# SSB_Transceiver_Driver_Amplifier.net
KiCad netlist of a schematic drawn in EAGLE
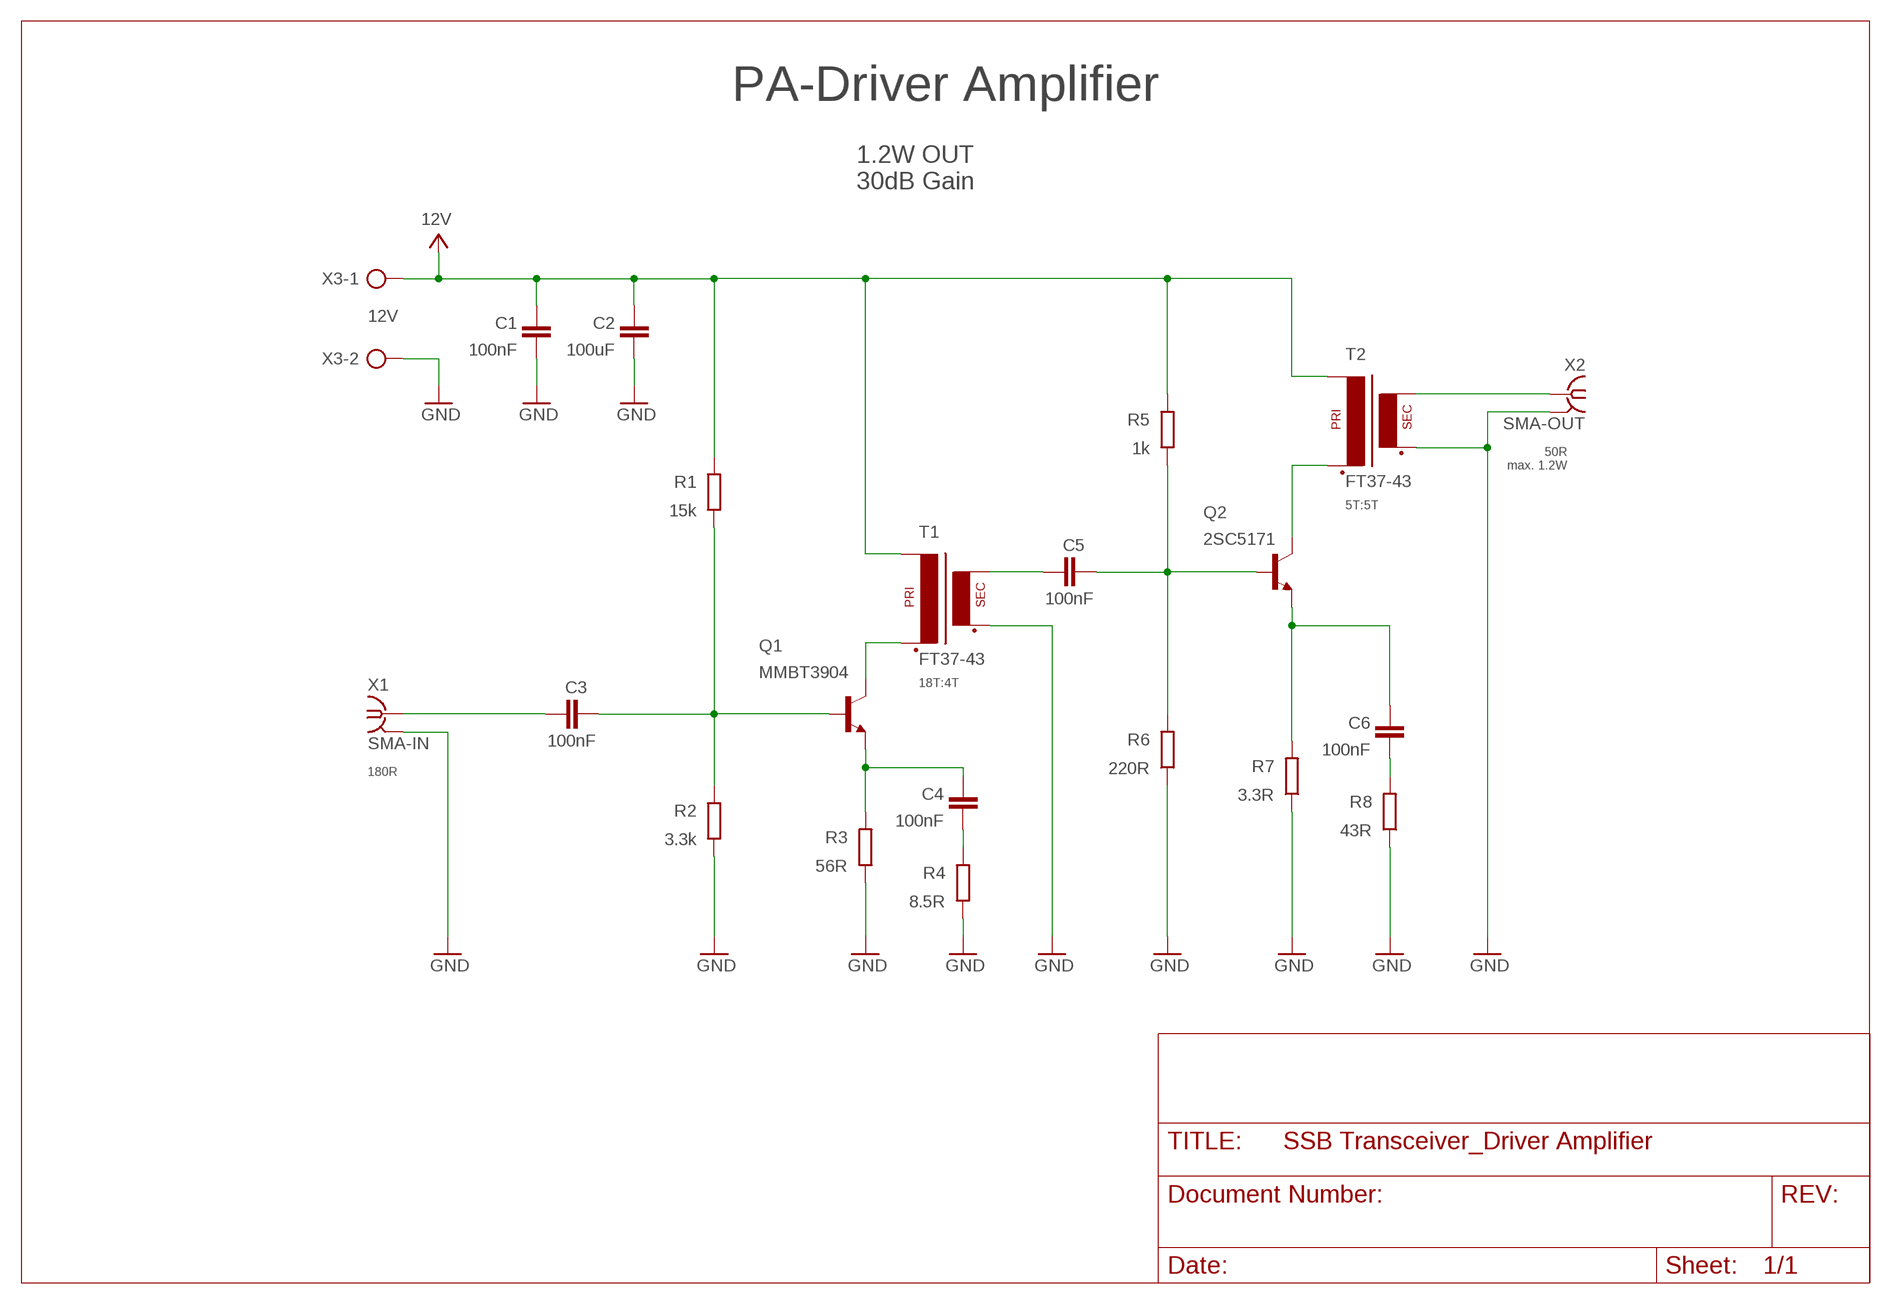
[diagram p0: schematic, sheet 1]

(export (version "E")
  (design (tool "Eeschema 10.0.6"))
  (components
    (comp (ref "C1")
      (value "100nF")
      (footprint "eagle-import:C0805")
      (libsource (lib "eagle-import") (part "C-EUC0805"))
    )
    (comp (ref "C2")
      (value "100uF")
      (footprint "eagle-import:C0805")
      (libsource (lib "eagle-import") (part "C-EUC0805"))
    )
    (comp (ref "C3")
      (value "100nF")
      (footprint "eagle-import:C0805")
      (libsource (lib "eagle-import") (part "C-EUC0805"))
    )
    (comp (ref "C4")
      (value "100nF")
      (footprint "eagle-import:C0805")
      (libsource (lib "eagle-import") (part "C-EUC0805"))
    )
    (comp (ref "C5")
      (value "100nF")
      (footprint "eagle-import:C0805")
      (libsource (lib "eagle-import") (part "C-EUC0805"))
    )
    (comp (ref "C6")
      (value "100nF")
      (footprint "eagle-import:C0805")
      (libsource (lib "eagle-import") (part "C-EUC0805"))
    )
    (comp (ref "Q1")
      (value "MMBT3904")
      (footprint "eagle-import:SOT23-BEC")
      (libsource (lib "eagle-import") (part "-NPN-SOT23-BECMMBT3904LT1"))
    )
    (comp (ref "Q2")
      (value "2SC5171")
      (footprint "eagle-import:TO220")
      (libsource (lib "eagle-import") (part "TIP31B"))
    )
    (comp (ref "R1")
      (value "15k")
      (footprint "eagle-import:R0805")
      (libsource (lib "eagle-import") (part "R-EU_R0805"))
    )
    (comp (ref "R2")
      (value "3.3k")
      (footprint "eagle-import:R0805")
      (libsource (lib "eagle-import") (part "R-EU_R0805"))
    )
    (comp (ref "R3")
      (value "56R")
      (footprint "eagle-import:R0805")
      (libsource (lib "eagle-import") (part "R-EU_R0805"))
    )
    (comp (ref "R4")
      (value "8.5R")
      (footprint "eagle-import:R0805")
      (libsource (lib "eagle-import") (part "R-EU_R0805"))
    )
    (comp (ref "R5")
      (value "1k")
      (footprint "eagle-import:R0805")
      (libsource (lib "eagle-import") (part "R-EU_R0805"))
    )
    (comp (ref "R6")
      (value "220R")
      (footprint "eagle-import:R0805")
      (libsource (lib "eagle-import") (part "R-EU_R0805"))
    )
    (comp (ref "R7")
      (value "3.3R")
      (footprint "eagle-import:R0805")
      (libsource (lib "eagle-import") (part "R-EU_R0805"))
    )
    (comp (ref "R8")
      (value "43R")
      (footprint "eagle-import:R0805")
      (libsource (lib "eagle-import") (part "R-EU_R0805"))
    )
    (comp (ref "T1")
      (value "FT37-43")
      (footprint "eagle-import:FT37-43SMD")
      (libsource (lib "eagle-import") (part "FT37-43"))
    )
    (comp (ref "T2")
      (value "FT37-43")
      (footprint "eagle-import:FT37-43SMD")
      (libsource (lib "eagle-import") (part "FT37-43"))
    )
    (comp (ref "X1")
      (value "SMA-IN")
      (footprint "eagle-import:J502-ND-142-0711-821_826")
      (fields (field (name "MF") "JOHNSON COMPONENTS") (field (name "MPN") "142-0711-821"))
      (libsource (lib "eagle-import") (part "SMA-PCB-CON142-0711-821/826"))
    )
    (comp (ref "X2")
      (value "SMA-OUT")
      (footprint "eagle-import:J502-ND-142-0711-821_826")
      (fields (field (name "MF") "JOHNSON COMPONENTS") (field (name "MPN") "142-0711-821"))
      (libsource (lib "eagle-import") (part "SMA-PCB-CON142-0711-821/826"))
    )
    (comp (ref "X3")
      (value "12V")
      (footprint "eagle-import:AK300_2")
      (libsource (lib "eagle-import") (part "AK300/2"))
    )
  )
  (nets
    (net (code "1") (name "12V") (class "Default")
      (node (ref "C1") (pin "2") (pinfunction "2_2") (pintype "passive"))
      (node (ref "C2") (pin "2") (pinfunction "2_2") (pintype "passive"))
      (node (ref "R1") (pin "1") (pinfunction "1_1") (pintype "passive"))
      (node (ref "R5") (pin "2") (pinfunction "2_2") (pintype "passive"))
      (node (ref "T1") (pin "P$1") (pinfunction "P1_P$1") (pintype "passive"))
      (node (ref "T2") (pin "P$1") (pinfunction "P1_P$1") (pintype "passive"))
      (node (ref "X3") (pin "1") (pinfunction "KL_1") (pintype "passive"))
    )
    (net (code "2") (name "GND") (class "Default")
      (node (ref "C1") (pin "1") (pinfunction "1_1") (pintype "passive"))
      (node (ref "C2") (pin "1") (pinfunction "1_1") (pintype "passive"))
      (node (ref "R2") (pin "2") (pinfunction "2_2") (pintype "passive"))
      (node (ref "R3") (pin "1") (pinfunction "1_1") (pintype "passive"))
      (node (ref "R4") (pin "1") (pinfunction "1_1") (pintype "passive"))
      (node (ref "R6") (pin "1") (pinfunction "1_1") (pintype "passive"))
      (node (ref "R7") (pin "1") (pinfunction "1_1") (pintype "passive"))
      (node (ref "R8") (pin "1") (pinfunction "1_1") (pintype "passive"))
      (node (ref "T1") (pin "S$2") (pinfunction "S2_S$2") (pintype "passive"))
      (node (ref "T2") (pin "S$2") (pinfunction "S2_S$2") (pintype "passive"))
      (node (ref "X1") (pin "G@1") (pinfunction "2_G@1") (pintype "passive"))
      (node (ref "X1") (pin "G@2") (pinfunction "2_G@2") (pintype "passive"))
      (node (ref "X1") (pin "G@3") (pinfunction "2_G@3") (pintype "passive"))
      (node (ref "X1") (pin "G@4") (pinfunction "2_G@4") (pintype "passive"))
      (node (ref "X2") (pin "G@1") (pinfunction "2_G@1") (pintype "passive"))
      (node (ref "X2") (pin "G@2") (pinfunction "2_G@2") (pintype "passive"))
      (node (ref "X2") (pin "G@3") (pinfunction "2_G@3") (pintype "passive"))
      (node (ref "X2") (pin "G@4") (pinfunction "2_G@4") (pintype "passive"))
      (node (ref "X3") (pin "2") (pinfunction "KL_2") (pintype "passive"))
    )
    (net (code "3") (name "Net-(C3-Pad1)") (class "Default")
      (node (ref "C3") (pin "1") (pinfunction "1_1") (pintype "passive"))
      (node (ref "Q1") (pin "B") (pinfunction "B_B") (pintype "passive"))
      (node (ref "R1") (pin "2") (pinfunction "2_2") (pintype "passive"))
      (node (ref "R2") (pin "1") (pinfunction "1_1") (pintype "passive"))
    )
    (net (code "4") (name "Net-(C3-Pad2)") (class "Default")
      (node (ref "C3") (pin "2") (pinfunction "2_2") (pintype "passive"))
      (node (ref "X1") (pin "1") (pinfunction "1_1") (pintype "passive"))
    )
    (net (code "5") (name "Net-(C4-Pad1)") (class "Default")
      (node (ref "C4") (pin "1") (pinfunction "1_1") (pintype "passive"))
      (node (ref "R4") (pin "2") (pinfunction "2_2") (pintype "passive"))
    )
    (net (code "6") (name "Net-(C4-Pad2)") (class "Default")
      (node (ref "C4") (pin "2") (pinfunction "2_2") (pintype "passive"))
      (node (ref "Q1") (pin "E") (pinfunction "E_E") (pintype "passive"))
      (node (ref "R3") (pin "2") (pinfunction "2_2") (pintype "passive"))
    )
    (net (code "7") (name "Net-(C6-Pad1)") (class "Default")
      (node (ref "C6") (pin "1") (pinfunction "1_1") (pintype "passive"))
      (node (ref "R8") (pin "2") (pinfunction "2_2") (pintype "passive"))
    )
    (net (code "8") (name "Net-(Q2-B)") (class "Default")
      (node (ref "C5") (pin "1") (pinfunction "1_1") (pintype "passive"))
      (node (ref "Q2") (pin "1") (pinfunction "B_1") (pintype "passive"))
      (node (ref "R5") (pin "1") (pinfunction "1_1") (pintype "passive"))
      (node (ref "R6") (pin "2") (pinfunction "2_2") (pintype "passive"))
    )
    (net (code "9") (name "Net-(Q2-C)") (class "Default")
      (node (ref "Q2") (pin "2") (pinfunction "C_2") (pintype "passive"))
      (node (ref "T2") (pin "P$2") (pinfunction "P2_P$2") (pintype "passive"))
    )
    (net (code "10") (name "Net-(Q2-E)") (class "Default")
      (node (ref "C6") (pin "2") (pinfunction "2_2") (pintype "passive"))
      (node (ref "Q2") (pin "3") (pinfunction "E_3") (pintype "passive"))
      (node (ref "R7") (pin "2") (pinfunction "2_2") (pintype "passive"))
    )
    (net (code "11") (name "Net-(T1-P2)") (class "Default")
      (node (ref "Q1") (pin "C") (pinfunction "C_C") (pintype "passive"))
      (node (ref "T1") (pin "P$2") (pinfunction "P2_P$2") (pintype "passive"))
    )
    (net (code "12") (name "Net-(T1-S1)") (class "Default")
      (node (ref "C5") (pin "2") (pinfunction "2_2") (pintype "passive"))
      (node (ref "T1") (pin "S$1") (pinfunction "S1_S$1") (pintype "passive"))
    )
    (net (code "13") (name "Net-(T2-S1)") (class "Default")
      (node (ref "T2") (pin "S$1") (pinfunction "S1_S$1") (pintype "passive"))
      (node (ref "X2") (pin "1") (pinfunction "1_1") (pintype "passive"))
    )
  )
)
